# untitled.net
KiCad netlist of a schematic drawn in EAGLE
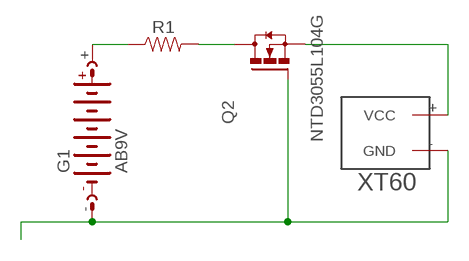
[diagram p0: schematic, sheet 1]

(export (version "E")
  (design (tool "Eeschema 10.0.6"))
  (components
    (comp (ref "G1")
      (value "AB9V")
      (footprint "eagle-import:AB9V")
      (libsource (lib "eagle-import") (part "AB9V"))
    )
    (comp (ref "Q2")
      (value "NTD3055L104G")
      (footprint "eagle-import:DPAK4")
      (fields (field (name "MANUFACTURER") "ON SEMICONDUCTORS") (field (name "CREATED_BY") "PCBLayout.com"))
      (libsource (lib "eagle-import") (part "NTD3055L104G"))
    )
    (comp (ref "R1")
      (value "RESISTORAXIAL-0.3-KIT")
      (footprint "eagle-import:AXIAL-0.3-KIT")
      (libsource (lib "eagle-import") (part "RESISTORAXIAL-0.3-KIT"))
    )
    (comp (ref "U$1")
      (value "XT60")
      (footprint "eagle-import:XT60")
      (libsource (lib "eagle-import") (part "XT60"))
    )
  )
  (nets
    (net (code "1") (name "Net-(Q2-G)") (class "Default")
      (node (ref "G1") (pin "-") (pinfunction "-_-") (pintype "passive"))
      (node (ref "Q2") (pin "1") (pinfunction "G_1") (pintype "passive"))
      (node (ref "U$1") (pin "-") (pinfunction "GND_-") (pintype "bidirectional"))
    )
    (net (code "2") (name "Net-(Q2-S)") (class "Default")
      (node (ref "Q2") (pin "3") (pinfunction "S_3") (pintype "passive"))
      (node (ref "U$1") (pin "+") (pinfunction "VCC_+") (pintype "bidirectional"))
    )
    (net (code "3") (name "Net-(R1-1)") (class "Default")
      (node (ref "G1") (pin "+") (pinfunction "+_+") (pintype "passive"))
      (node (ref "R1") (pin "P$1") (pinfunction "1_P$1") (pintype "passive"))
    )
    (net (code "4") (name "Net-(R1-2)") (class "Default")
      (node (ref "Q2") (pin "2") (pinfunction "D_2") (pintype "passive"))
      (node (ref "Q2") (pin "4") (pinfunction "D_4") (pintype "passive"))
      (node (ref "R1") (pin "P$2") (pinfunction "2_P$2") (pintype "passive"))
    )
  )
)
